# 3796.net
KiCad netlist of a schematic drawn in Altium Designer
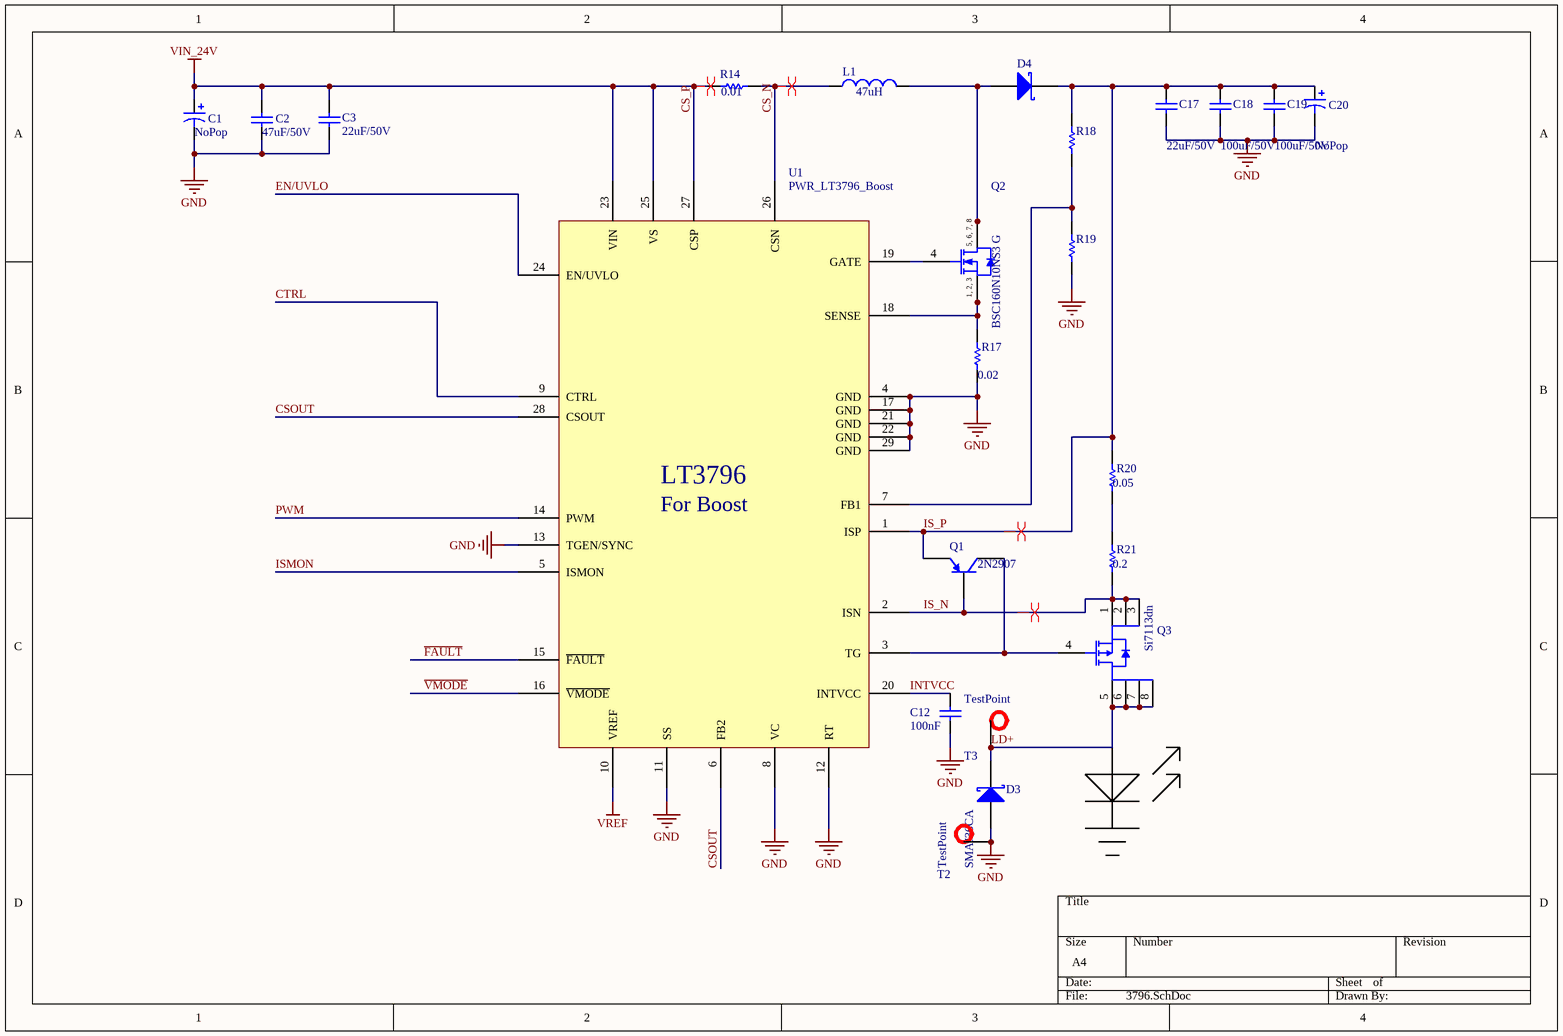
[diagram p0: 3796.SchDoc]

(export (version "E")
  (design (tool "Eeschema 10.0.6"))
  (components
    (comp (ref "C1")
      (value "NoPop")
      (footprint "SMC_Altium Capacity 8*10")
      (description "Polarized Capacitor (Radial)")
      (fields (field (name "PUBLISHER") "Altium Limited"))
      (libsource (lib "Miscellaneous Devices") (part "Cap Pol1"))
    )
    (comp (ref "C2")
      (value "47uF/50V")
      (footprint "1206[3216] - NP")
      (description "Capacitor")
      (fields (field (name "PUBLISHER") "Altium Limited"))
      (libsource (lib "Miscellaneous Devices") (part "Cap"))
    )
    (comp (ref "C3")
      (value "22uF/50V")
      (footprint "1206[3216] - NP")
      (description "Capacitor")
      (fields (field (name "PUBLISHER") "Altium Limited"))
      (libsource (lib "Miscellaneous Devices") (part "Cap"))
    )
    (comp (ref "C12")
      (value "100nF")
      (footprint "1608[0603]")
      (description "Capacitor")
      (fields (field (name "PUBLISHER") "Altium Limited"))
      (libsource (lib "Miscellaneous Devices") (part "Cap"))
    )
    (comp (ref "C17")
      (value "22uF/50V")
      (footprint "1206[3216] - NP")
      (description "Capacitor")
      (fields (field (name "PUBLISHER") "Altium Limited"))
      (libsource (lib "Miscellaneous Devices") (part "Cap"))
    )
    (comp (ref "C18")
      (value "100uF/50V")
      (footprint "1206[3216] - NP")
      (description "Capacitor")
      (fields (field (name "PUBLISHER") "Altium Limited"))
      (libsource (lib "Miscellaneous Devices") (part "Cap"))
    )
    (comp (ref "C19")
      (value "100uF/50V")
      (footprint "1206[3216] - NP")
      (description "Capacitor")
      (fields (field (name "PUBLISHER") "Altium Limited"))
      (libsource (lib "Miscellaneous Devices") (part "Cap"))
    )
    (comp (ref "C20")
      (value "NoPop")
      (footprint "SMC_Altium Capacity 8*10")
      (description "Polarized Capacitor (Radial)")
      (fields (field (name "PUBLISHER") "Altium Limited"))
      (libsource (lib "Miscellaneous Devices") (part "Cap Pol1"))
    )
    (comp (ref "D3")
      (value "SMAJ36CA")
      (footprint "SMA_DIOM5226X26N")
      (description "Schottky Diode")
      (fields (field (name "PUBLISHER") "Altium Limited"))
      (libsource (lib "Miscellaneous Devices") (part "D Schottky"))
    )
    (comp (ref "D4")
      (value "~")
      (footprint "PowerDI5")
      (description "Schottky Diode")
      (fields (field (name "PUBLISHER") "Altium Limited"))
      (libsource (lib "Miscellaneous Devices") (part "D Schottky"))
    )
    (comp (ref "L1")
      (value "47uH")
      (footprint "Laser-LiuXin:IHLP4040")
      (description "Inductor")
      (fields (field (name "Comment") "IHLP-4040DZ-11") (field (name "PUBLISHER") "Altium Limited"))
      (libsource (lib "Miscellaneous Devices") (part "Inductor"))
    )
    (comp (ref "Q1")
      (value "2N2907")
      (footprint "SOT95P280X115-3N")
      (description "PNP General Purpose Amplifier")
      (fields (field (name "PUBLISHER") "Altium Limited"))
      (libsource (lib "Miscellaneous Devices") (part "2N3906"))
    )
    (comp (ref "Q2")
      (value "BSC160N10NS3 G")
      (footprint "INF-PG-TDSON-8-1_V")
      (fields (field (name "MANUFACTURER") "Infineon"))
      (libsource (lib "BSC160N10NS3 G") (part "BSC160N10NS3 G"))
    )
    (comp (ref "Q3")
      (value "Si7113dn")
      (footprint "1212-8 Single")
      (description "PMOS, Si7113dn")
      (fields (field (name "MANUFACTURER") "Infineon") (field (name "PARTNUMBER") "BSC160N10NS3 G"))
      (libsource (lib "Laser-LiuXin") (part "PWR_ Si7113dn"))
    )
    (comp (ref "R14")
      (value "0.01")
      (footprint "2512[6432]")
      (description "Resistor")
      (fields (field (name "PUBLISHER") "Altium Limited"))
      (libsource (lib "Miscellaneous Devices") (part "Res1"))
    )
    (comp (ref "R17")
      (value "0.02")
      (footprint "2512[6432]")
      (description "Resistor")
      (fields (field (name "PUBLISHER") "Altium Limited"))
      (libsource (lib "Miscellaneous Devices") (part "Res1"))
    )
    (comp (ref "R18")
      (value "~")
      (footprint "1608[0603]")
      (description "Resistor")
      (fields (field (name "PUBLISHER") "Altium Limited"))
      (libsource (lib "Miscellaneous Devices") (part "Res1"))
    )
    (comp (ref "R19")
      (value "~")
      (footprint "1608[0603]")
      (description "Resistor")
      (fields (field (name "PUBLISHER") "Altium Limited"))
      (libsource (lib "Miscellaneous Devices") (part "Res1"))
    )
    (comp (ref "R20")
      (value "0.05")
      (footprint "2512[6432]")
      (description "Resistor")
      (fields (field (name "PUBLISHER") "Altium Limited"))
      (libsource (lib "Miscellaneous Devices") (part "Res1"))
    )
    (comp (ref "R21")
      (value "0.2")
      (footprint "2512[6432]")
      (description "Resistor")
      (fields (field (name "PUBLISHER") "Altium Limited"))
      (libsource (lib "Miscellaneous Devices") (part "Res1"))
    )
    (comp (ref "T2")
      (value "Test Point")
      (footprint "TestPoint")
      (libsource (lib "Laser-LiuXin") (part "TP"))
    )
    (comp (ref "T3")
      (value "Test Point")
      (footprint "TestPoint")
      (libsource (lib "Laser-LiuXin") (part "TP"))
    )
    (comp (ref "U1")
      (value "PWR_LT3796_Boost")
      (footprint "TSOP65P640X120_HS-29N")
      (description "100V Constant-Current and   Constant-Voltage Controller   with Dual Current Sense")
      (libsource (lib "Laser-LiuXin") (part "PWR_LT3796_Boost"))
    )
  )
  (nets
    (net (code "1") (name "/CSOUT") (class "Default")
      (node (ref "U1") (pin "28") (pinfunction "CSOUT_28") (pintype "passive"))
      (node (ref "U1") (pin "6") (pinfunction "FB2_6") (pintype "passive"))
    )
    (net (code "2") (name "/CS_N") (class "Default")
      (node (ref "L1") (pin "1") (pinfunction "1_1") (pintype "passive"))
      (node (ref "R14") (pin "2") (pinfunction "2_2") (pintype "passive"))
      (node (ref "U1") (pin "26") (pinfunction "CSN_26") (pintype "passive"))
    )
    (net (code "3") (name "/CTRL") (class "Default")
      (node (ref "U1") (pin "9") (pinfunction "CTRL_9") (pintype "passive"))
    )
    (net (code "4") (name "/EN{slash}UVLO") (class "Default")
      (node (ref "U1") (pin "24") (pinfunction "EN/UVLO_24") (pintype "passive"))
    )
    (net (code "5") (name "/INTVCC") (class "Default")
      (node (ref "C12") (pin "1") (pinfunction "1_1") (pintype "passive"))
      (node (ref "U1") (pin "20") (pinfunction "INTVCC_20") (pintype "passive"))
    )
    (net (code "6") (name "/ISMON") (class "Default")
      (node (ref "U1") (pin "5") (pinfunction "ISMON_5") (pintype "passive"))
    )
    (net (code "7") (name "/IS_N") (class "Default")
      (node (ref "Q1") (pin "2") (pinfunction "B_2") (pintype "passive"))
      (node (ref "Q3") (pin "1") (pinfunction "SOURCE_1") (pintype "passive"))
      (node (ref "Q3") (pin "2") (pinfunction "SOURCE_2") (pintype "passive"))
      (node (ref "Q3") (pin "3") (pinfunction "SOURCE_3") (pintype "passive"))
      (node (ref "R21") (pin "1") (pinfunction "1_1") (pintype "passive"))
      (node (ref "U1") (pin "2") (pinfunction "ISN_2") (pintype "passive"))
    )
    (net (code "8") (name "/IS_P") (class "Default")
      (node (ref "C17") (pin "2") (pinfunction "2_2") (pintype "passive"))
      (node (ref "C18") (pin "2") (pinfunction "2_2") (pintype "passive"))
      (node (ref "C19") (pin "2") (pinfunction "2_2") (pintype "passive"))
      (node (ref "C20") (pin "1") (pinfunction "1_1") (pintype "passive"))
      (node (ref "D4") (pin "2") (pinfunction "K_2") (pintype "passive"))
      (node (ref "Q1") (pin "1") (pinfunction "E_1") (pintype "passive"))
      (node (ref "R18") (pin "2") (pinfunction "2_2") (pintype "passive"))
      (node (ref "R20") (pin "2") (pinfunction "2_2") (pintype "passive"))
      (node (ref "U1") (pin "1") (pinfunction "ISP_1") (pintype "passive"))
    )
    (net (code "9") (name "/LD+") (class "Default")
      (node (ref "D3") (pin "2") (pinfunction "K_2") (pintype "passive"))
      (node (ref "Q3") (pin "5") (pinfunction "DRAIN_5") (pintype "passive"))
      (node (ref "Q3") (pin "6") (pinfunction "DRAIN_6") (pintype "passive"))
      (node (ref "Q3") (pin "7") (pinfunction "DRAIN_7") (pintype "passive"))
      (node (ref "Q3") (pin "8") (pinfunction "DRAIN_8") (pintype "passive"))
      (node (ref "T3") (pin "1") (pinfunction "TP_1") (pintype "passive"))
    )
    (net (code "10") (name "/PWM") (class "Default")
      (node (ref "U1") (pin "14") (pinfunction "PWM_14") (pintype "passive"))
    )
    (net (code "11") (name "/~{FAULT}") (class "Default")
      (node (ref "U1") (pin "15") (pinfunction "~{FAULT}_15") (pintype "passive"))
    )
    (net (code "12") (name "/~{VMODE}") (class "Default")
      (node (ref "U1") (pin "16") (pinfunction "~{VMODE}_16") (pintype "passive"))
    )
    (net (code "13") (name "GND") (class "Default")
      (node (ref "C1") (pin "2") (pinfunction "2_2") (pintype "passive"))
      (node (ref "C12") (pin "2") (pinfunction "2_2") (pintype "passive"))
      (node (ref "C17") (pin "1") (pinfunction "1_1") (pintype "passive"))
      (node (ref "C18") (pin "1") (pinfunction "1_1") (pintype "passive"))
      (node (ref "C19") (pin "1") (pinfunction "1_1") (pintype "passive"))
      (node (ref "C2") (pin "1") (pinfunction "1_1") (pintype "passive"))
      (node (ref "C20") (pin "2") (pinfunction "2_2") (pintype "passive"))
      (node (ref "C3") (pin "1") (pinfunction "1_1") (pintype "passive"))
      (node (ref "D3") (pin "1") (pinfunction "A_1") (pintype "passive"))
      (node (ref "R17") (pin "1") (pinfunction "1_1") (pintype "passive"))
      (node (ref "R19") (pin "2") (pinfunction "2_2") (pintype "passive"))
      (node (ref "T2") (pin "1") (pinfunction "TP_1") (pintype "passive"))
      (node (ref "U1") (pin "11") (pinfunction "SS_11") (pintype "passive"))
      (node (ref "U1") (pin "12") (pinfunction "RT_12") (pintype "passive"))
      (node (ref "U1") (pin "13") (pinfunction "TGEN/SYNC_13") (pintype "passive"))
      (node (ref "U1") (pin "17") (pinfunction "GND_17") (pintype "passive"))
      (node (ref "U1") (pin "21") (pinfunction "GND_21") (pintype "passive"))
      (node (ref "U1") (pin "22") (pinfunction "GND_22") (pintype "passive"))
      (node (ref "U1") (pin "29") (pinfunction "GND_29") (pintype "passive"))
      (node (ref "U1") (pin "4") (pinfunction "GND_4") (pintype "passive"))
      (node (ref "U1") (pin "8") (pinfunction "VC_8") (pintype "passive"))
    )
    (net (code "14") (name "Net-(D4-A)") (class "Default")
      (node (ref "D4") (pin "1") (pinfunction "A_1") (pintype "passive"))
      (node (ref "L1") (pin "2") (pinfunction "2_2") (pintype "passive"))
      (node (ref "Q2") (pin "5") (pinfunction "DRAIN_5") (pintype "passive"))
      (node (ref "Q2") (pin "6") (pinfunction "DRAIN_6") (pintype "passive"))
      (node (ref "Q2") (pin "7") (pinfunction "DRAIN_7") (pintype "passive"))
      (node (ref "Q2") (pin "8") (pinfunction "DRAIN_8") (pintype "passive"))
    )
    (net (code "15") (name "Net-(Q1-C)") (class "Default")
      (node (ref "Q1") (pin "3") (pinfunction "C_3") (pintype "passive"))
      (node (ref "Q3") (pin "4") (pinfunction "GATE_4") (pintype "passive"))
      (node (ref "U1") (pin "3") (pinfunction "TG_3") (pintype "passive"))
    )
    (net (code "16") (name "Net-(Q2-GATE)") (class "Default")
      (node (ref "Q2") (pin "4") (pinfunction "GATE_4") (pintype "passive"))
      (node (ref "U1") (pin "19") (pinfunction "GATE_19") (pintype "passive"))
    )
    (net (code "17") (name "Net-(R20-Pad1)") (class "Default")
      (node (ref "R20") (pin "1") (pinfunction "1_1") (pintype "passive"))
      (node (ref "R21") (pin "2") (pinfunction "2_2") (pintype "passive"))
    )
    (net (code "18") (name "Net-(U1-FB1)") (class "Default")
      (node (ref "R18") (pin "1") (pinfunction "1_1") (pintype "passive"))
      (node (ref "R19") (pin "1") (pinfunction "1_1") (pintype "passive"))
      (node (ref "U1") (pin "7") (pinfunction "FB1_7") (pintype "passive"))
    )
    (net (code "19") (name "Net-(U1-SENSE)") (class "Default")
      (node (ref "Q2") (pin "1") (pinfunction "SOURCE_1") (pintype "passive"))
      (node (ref "Q2") (pin "2") (pinfunction "SOURCE_2") (pintype "passive"))
      (node (ref "Q2") (pin "3") (pinfunction "SOURCE_3") (pintype "passive"))
      (node (ref "R17") (pin "2") (pinfunction "2_2") (pintype "passive"))
      (node (ref "U1") (pin "18") (pinfunction "SENSE_18") (pintype "passive"))
    )
    (net (code "20") (name "VIN_24V") (class "Default")
      (node (ref "C1") (pin "1") (pinfunction "1_1") (pintype "passive"))
      (node (ref "C2") (pin "2") (pinfunction "2_2") (pintype "passive"))
      (node (ref "C3") (pin "2") (pinfunction "2_2") (pintype "passive"))
      (node (ref "R14") (pin "1") (pinfunction "1_1") (pintype "passive"))
      (node (ref "U1") (pin "23") (pinfunction "VIN_23") (pintype "power_in"))
      (node (ref "U1") (pin "25") (pinfunction "VS_25") (pintype "passive"))
      (node (ref "U1") (pin "27") (pinfunction "CSP_27") (pintype "passive"))
    )
    (net (code "21") (name "VREF") (class "Default")
      (node (ref "U1") (pin "10") (pinfunction "VREF_10") (pintype "passive"))
    )
  )
)
